# Power.net
KiCad netlist of a schematic drawn in Altium Designer
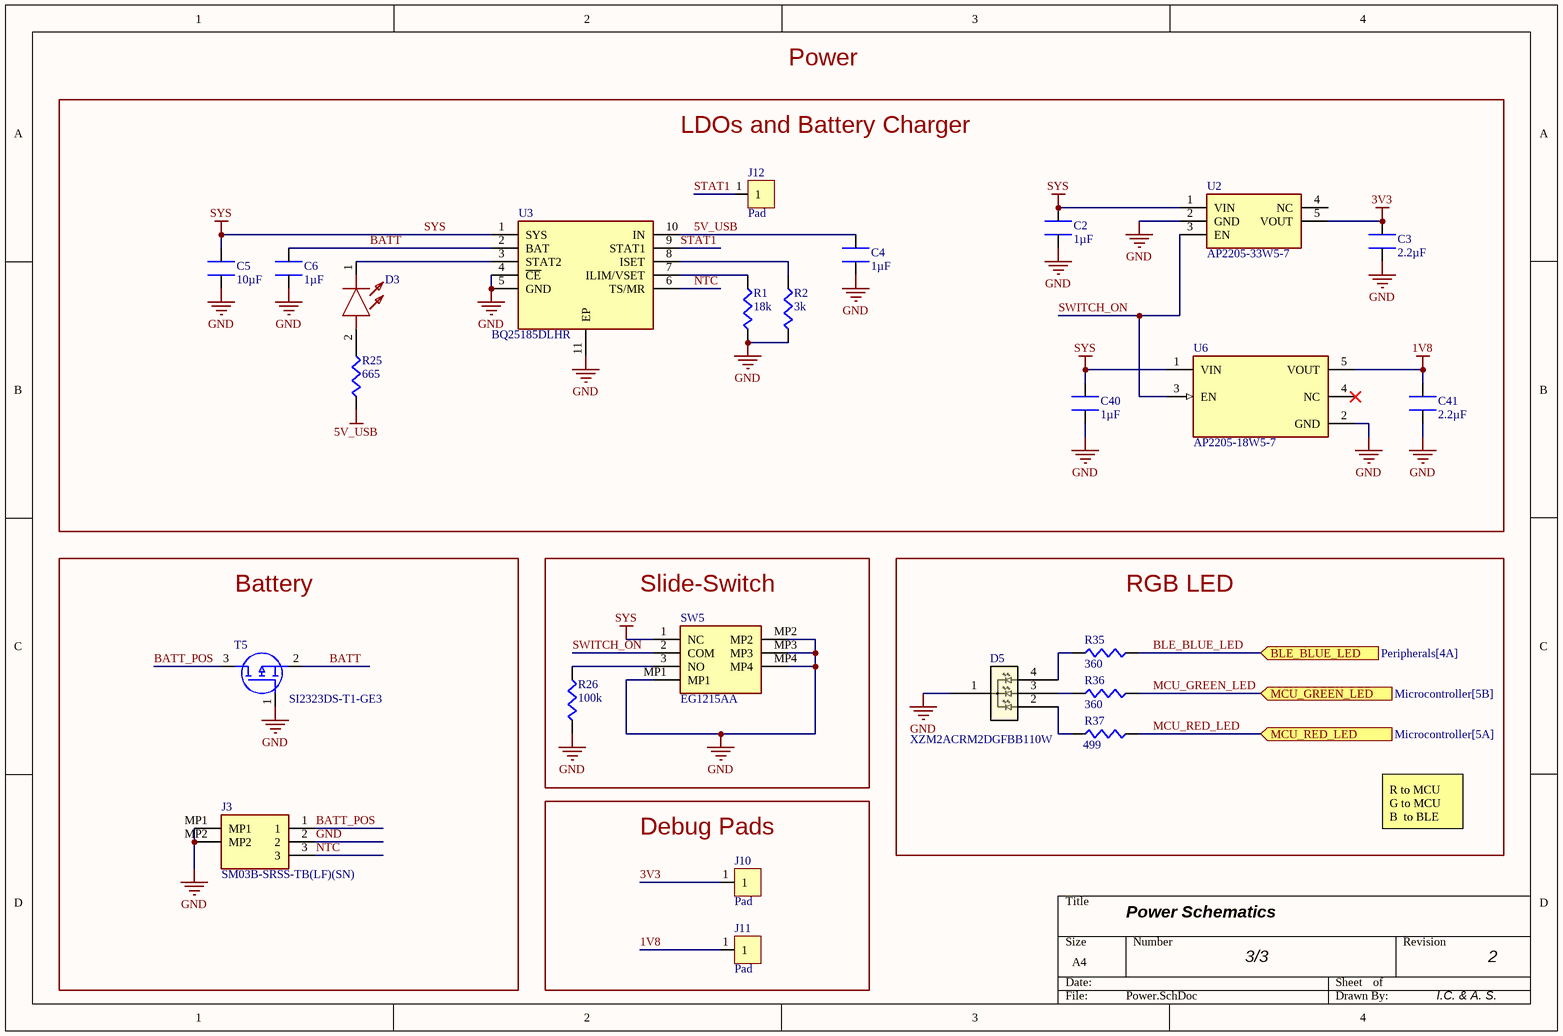
[diagram p0: Power.SchDoc]

(export (version "E")
  (design (tool "Eeschema 10.0.6"))
  (components
    (comp (ref "C2")
      (value "1µF")
      (footprint "Chip2PinSM127P600-8N")
      (fields (field (name "Comment") "0402YD105KAT4A"))
      (libsource (lib "Workspace LAB SEL") (part "Generic capacitor"))
    )
    (comp (ref "C3")
      (value "2.2µF")
      (footprint "Chip2PinSM127P600-8N")
      (fields (field (name "Comment") "LMK105BJ225MV-F"))
      (libsource (lib "Workspace LAB SEL") (part "Generic capacitor"))
    )
    (comp (ref "C4")
      (value "1µF")
      (footprint "Chip2PinSM127P600-8N")
      (fields (field (name "Comment") "CL03A105KP3NSNC"))
      (libsource (lib "Workspace LAB SEL") (part "Generic capacitor"))
    )
    (comp (ref "C5")
      (value "10µF")
      (footprint "Chip2PinSM127P600-8N")
      (fields (field (name "Comment") "0402ZD106MAT2A"))
      (libsource (lib "Workspace LAB SEL") (part "Generic capacitor"))
    )
    (comp (ref "C6")
      (value "1µF")
      (footprint "Chip2PinSM127P600-8N")
      (fields (field (name "Comment") "CL03A105KP3NSNC"))
      (libsource (lib "Workspace LAB SEL") (part "Generic capacitor"))
    )
    (comp (ref "C40")
      (value "1µF")
      (footprint "Chip2PinSM127P600-8N")
      (fields (field (name "Comment") "0402YD105KAT4A"))
      (libsource (lib "Workspace LAB SEL") (part "Generic capacitor"))
    )
    (comp (ref "C41")
      (value "2.2µF")
      (footprint "Chip2PinSM127P600-8N")
      (fields (field (name "Comment") "LMK105BJ225MV-F"))
      (libsource (lib "Workspace LAB SEL") (part "Generic capacitor"))
    )
    (comp (ref "D3")
      (value "KS EELP41.22-P1R2-58-A8J8-020-R18")
      (footprint "KS EELP41.22-P1R2-58-A8J8-020-R18-Footprint-1")
      (description "Single Colour LEDs")
      (libsource (lib "Workspace LAB SEL") (part "KS EELP41.22-P1R2-58-A8J8-020-R18-Symbol-1"))
    )
    (comp (ref "D5")
      (value "XZM2ACRM2DGFBB110W")
      (footprint "XZM2ACRM2DGFBB110W-Footprint-1")
      (description "1.6X1.6MM Rgb Full Color SMD Led")
      (libsource (lib "Workspace LAB SEL") (part "XZM2ACRM2DGFBB110W-Symbol-1"))
    )
    (comp (ref "J3")
      (value "SM03B-SRSS-TB(LF)(SN)")
      (footprint "SM03B-SRSS-TB(LF)(SN)-Footprint-1")
      (description "Connector Header, Side Entry, SR Series, 3 Position, 1.00mm, 50V, Surface Mount, Tin, Natural")
      (libsource (lib "Workspace LAB SEL") (part "SM03B-SRSS-TB(LF)(SN)-Symbol-1"))
    )
    (comp (ref "J10")
      (value "Pad")
      (footprint "Pad-Footprint-1")
      (description "Pad to connect external electrodes or sensors. Choose the right footprint.")
      (libsource (lib "Workspace LAB SEL") (part "Pad-Symbol-1"))
    )
    (comp (ref "J11")
      (value "Pad")
      (footprint "Pad-Footprint-1")
      (description "Pad to connect external electrodes or sensors. Choose the right footprint.")
      (libsource (lib "Workspace LAB SEL") (part "Pad-Symbol-1"))
    )
    (comp (ref "J12")
      (value "Pad")
      (footprint "Pad-Footprint-1")
      (description "Pad to connect external electrodes or sensors. Choose the right footprint.")
      (libsource (lib "Workspace LAB SEL") (part "Pad-Symbol-1"))
    )
    (comp (ref "R1")
      (value "18k")
      (footprint "Chip2PinSM127P600-8N")
      (description "Fixed Resistor, Thin Film, 0.05W, 18000ohm, 25V, 0.1% +/-Tol, 25ppm/Cel, Surface Mount, 0201")
      (fields (field (name "TOLERANCE") "0.1%") (field (name "Comment") "TNPW020118K0BEED"))
      (libsource (lib "Workspace LAB SEL") (part "Generic resistor"))
    )
    (comp (ref "R2")
      (value "3k")
      (footprint "Chip2PinSM127P600-8N")
      (description "Fixed Resistor, Thin Film, 0.05W, 3000ohm, 25V, 0.1% +/-Tol, 25ppm/Cel, Surface Mount, 0201")
      (fields (field (name "TOLERANCE") "0.1%") (field (name "Comment") "TNPW02013K00BEED"))
      (libsource (lib "Workspace LAB SEL") (part "Generic resistor"))
    )
    (comp (ref "R25")
      (value "665")
      (footprint "Chip2PinSM127P600-8N")
      (fields
        (field (name "TOLERANCE") "1%")
        (field (name "POWER") "50mW")
        (field (name "Comment") "CRCW0201665RFKED")
      )
      (libsource (lib "Workspace LAB SEL") (part "Generic resistor"))
    )
    (comp (ref "R26")
      (value "100k")
      (footprint "Chip2PinSM127P600-8N")
      (fields
        (field (name "POWER") "50mW")
        (field (name "TOLERANCE") "5%")
        (field (name "Comment") "ERJ-1GNJ104C")
      )
      (libsource (lib "Workspace LAB SEL") (part "Generic resistor"))
    )
    (comp (ref "R35")
      (value "360")
      (footprint "Chip2PinSM127P600-8N")
      (fields
        (field (name "TOLERANCE") "1%")
        (field (name "POWER") "50mW")
        (field (name "Comment") "CRCW0201360RFKED")
      )
      (libsource (lib "Workspace LAB SEL") (part "Generic resistor"))
    )
    (comp (ref "R36")
      (value "360")
      (footprint "Chip2PinSM127P600-8N")
      (fields
        (field (name "TOLERANCE") "1%")
        (field (name "POWER") "50mW")
        (field (name "Comment") "CRCW0201360RFKED")
      )
      (libsource (lib "Workspace LAB SEL") (part "Generic resistor"))
    )
    (comp (ref "R37")
      (value "499")
      (footprint "Chip2PinSM127P600-8N")
      (description "0201 Thin film chip resistor 0201 SMD Resistor 0.1% 25ppm 499ohm")
      (fields (field (name "Comment") "ERA-1AEB4990C"))
      (libsource (lib "Workspace LAB SEL") (part "Generic resistor"))
    )
    (comp (ref "SW5")
      (value "EG1215AA")
      (footprint "EG1215AA-Footprint-1")
      (description "Slide Switch")
      (libsource (lib "Workspace LAB SEL") (part "EG1215AA-Symbol-1"))
    )
    (comp (ref "T5")
      (value "SI2323DS-T1-GE3")
      (footprint "SI2323DS-T1-GE3-Footprint-1")
      (libsource (lib "Workspace LAB SEL") (part "SI2323DS-T1-GE3-Symbol-1"))
    )
    (comp (ref "U2")
      (value "AP2205-33W5-7")
      (footprint "AP2205-33W5-7-Footprint-1")
      (description "Fixed LDO Voltage Regulator, 2.3V to 24V in, 360mV Drop, 3.3V out, 200mA out, SOT-25-5")
      (libsource (lib "Workspace LAB SEL") (part "AP2205-33W5-7-Symbol-1"))
    )
    (comp (ref "U3")
      (value "BQ25185DLHR")
      (footprint "BQ25185DLHR-Footprint-1")
      (libsource (lib "Workspace LAB SEL") (part "BQ25185DLHR-Symbol-1"))
    )
    (comp (ref "U6")
      (value "AP2205-18W5-7")
      (footprint "AP2205-18W5-7-Footprint-1")
      (description "LDO Voltage Regulators LDO CMOS LowCurr. 1.8V fixed")
      (libsource (lib "Workspace LAB SEL") (part "AP2205-18W5-7-Symbol-1"))
    )
  )
  (nets
    (net (code "1") (name "/BATT") (class "Default")
      (node (ref "C6") (pin "2") (pinfunction "2_2") (pintype "passive"))
      (node (ref "T5") (pin "2") (pinfunction "S_2") (pintype "passive"))
      (node (ref "U3") (pin "2") (pinfunction "BAT_2") (pintype "passive"))
    )
    (net (code "2") (name "/BATT_POS") (class "Default")
      (node (ref "J3") (pin "1") (pinfunction "1_1") (pintype "passive"))
      (node (ref "T5") (pin "3") (pinfunction "D_3") (pintype "passive"))
    )
    (net (code "3") (name "/BLE_BLUE_LED") (class "Default")
      (node (ref "R35") (pin "2") (pinfunction "2_2") (pintype "passive"))
    )
    (net (code "4") (name "/MCU_GREEN_LED") (class "Default")
      (node (ref "R36") (pin "2") (pinfunction "2_2") (pintype "passive"))
    )
    (net (code "5") (name "/MCU_RED_LED") (class "Default")
      (node (ref "R37") (pin "2") (pinfunction "2_2") (pintype "passive"))
    )
    (net (code "6") (name "/NTC") (class "Default")
      (node (ref "J3") (pin "3") (pinfunction "3_3") (pintype "passive"))
      (node (ref "U3") (pin "6") (pinfunction "TS/MR_6") (pintype "passive"))
    )
    (net (code "7") (name "/STAT1") (class "Default")
      (node (ref "J12") (pin "1") (pinfunction "1_1") (pintype "passive"))
      (node (ref "U3") (pin "9") (pinfunction "STAT1_9") (pintype "passive"))
    )
    (net (code "8") (name "/SWITCH_ON") (class "Default")
      (node (ref "SW5") (pin "2") (pinfunction "COM_2") (pintype "passive"))
      (node (ref "U2") (pin "3") (pinfunction "EN_3") (pintype "passive"))
      (node (ref "U6") (pin "3") (pinfunction "EN_3") (pintype "input"))
    )
    (net (code "9") (name "1V8") (class "Default")
      (node (ref "C41") (pin "2") (pinfunction "2_2") (pintype "passive"))
      (node (ref "J11") (pin "1") (pinfunction "1_1") (pintype "passive"))
      (node (ref "U6") (pin "5") (pinfunction "VOUT_5") (pintype "power_in"))
    )
    (net (code "10") (name "3V3") (class "Default")
      (node (ref "C3") (pin "2") (pinfunction "2_2") (pintype "passive"))
      (node (ref "J10") (pin "1") (pinfunction "1_1") (pintype "passive"))
      (node (ref "U2") (pin "5") (pinfunction "VOUT_5") (pintype "passive"))
    )
    (net (code "11") (name "5V_USB") (class "Default")
      (node (ref "C4") (pin "2") (pinfunction "2_2") (pintype "passive"))
      (node (ref "R25") (pin "1") (pinfunction "1_1") (pintype "passive"))
      (node (ref "U3") (pin "10") (pinfunction "IN_10") (pintype "passive"))
    )
    (net (code "12") (name "GND") (class "Default")
      (node (ref "C2") (pin "1") (pinfunction "1_1") (pintype "passive"))
      (node (ref "C3") (pin "1") (pinfunction "1_1") (pintype "passive"))
      (node (ref "C4") (pin "1") (pinfunction "1_1") (pintype "passive"))
      (node (ref "C40") (pin "1") (pinfunction "1_1") (pintype "passive"))
      (node (ref "C41") (pin "1") (pinfunction "1_1") (pintype "passive"))
      (node (ref "C5") (pin "2") (pinfunction "2_2") (pintype "passive"))
      (node (ref "C6") (pin "1") (pinfunction "1_1") (pintype "passive"))
      (node (ref "D5") (pin "1") (pinfunction "1_1") (pintype "passive"))
      (node (ref "J3") (pin "2") (pinfunction "2_2") (pintype "passive"))
      (node (ref "J3") (pin "MP1") (pinfunction "MP1_MP1") (pintype "passive"))
      (node (ref "J3") (pin "MP2") (pinfunction "MP2_MP2") (pintype "passive"))
      (node (ref "R1") (pin "1") (pinfunction "1_1") (pintype "passive"))
      (node (ref "R2") (pin "1") (pinfunction "1_1") (pintype "passive"))
      (node (ref "R26") (pin "1") (pinfunction "1_1") (pintype "passive"))
      (node (ref "SW5") (pin "MP1") (pinfunction "MP1_MP1") (pintype "passive"))
      (node (ref "SW5") (pin "MP2") (pinfunction "MP2_MP2") (pintype "passive"))
      (node (ref "SW5") (pin "MP3") (pinfunction "MP3_MP3") (pintype "passive"))
      (node (ref "SW5") (pin "MP4") (pinfunction "MP4_MP4") (pintype "passive"))
      (node (ref "T5") (pin "1") (pinfunction "G_1") (pintype "passive"))
      (node (ref "U2") (pin "2") (pinfunction "GND_2") (pintype "passive"))
      (node (ref "U3") (pin "11") (pinfunction "EP_11") (pintype "passive"))
      (node (ref "U3") (pin "4") (pinfunction "~{CE}_4") (pintype "passive"))
      (node (ref "U3") (pin "5") (pinfunction "GND_5") (pintype "passive"))
      (node (ref "U6") (pin "2") (pinfunction "GND_2") (pintype "power_in"))
    )
    (net (code "13") (name "Net-(D3-A)") (class "Default")
      (node (ref "D3") (pin "2") (pinfunction "A_2") (pintype "passive"))
      (node (ref "R25") (pin "2") (pinfunction "2_2") (pintype "passive"))
    )
    (net (code "14") (name "Net-(D3-K)") (class "Default")
      (node (ref "D3") (pin "1") (pinfunction "K_1") (pintype "passive"))
      (node (ref "U3") (pin "3") (pinfunction "STAT2_3") (pintype "passive"))
    )
    (net (code "15") (name "Net-(D5-Pad2)") (class "Default")
      (node (ref "D5") (pin "2") (pinfunction "2_2") (pintype "passive"))
      (node (ref "R37") (pin "1") (pinfunction "1_1") (pintype "passive"))
    )
    (net (code "16") (name "Net-(D5-Pad3)") (class "Default")
      (node (ref "D5") (pin "3") (pinfunction "3_3") (pintype "passive"))
      (node (ref "R36") (pin "1") (pinfunction "1_1") (pintype "passive"))
    )
    (net (code "17") (name "Net-(D5-Pad4)") (class "Default")
      (node (ref "D5") (pin "4") (pinfunction "4_4") (pintype "passive"))
      (node (ref "R35") (pin "1") (pinfunction "1_1") (pintype "passive"))
    )
    (net (code "18") (name "Net-(SW5-NO)") (class "Default")
      (node (ref "R26") (pin "2") (pinfunction "2_2") (pintype "passive"))
      (node (ref "SW5") (pin "3") (pinfunction "NO_3") (pintype "passive"))
    )
    (net (code "19") (name "Net-(U3-ILIM{slash}VSET)") (class "Default")
      (node (ref "R1") (pin "2") (pinfunction "2_2") (pintype "passive"))
      (node (ref "U3") (pin "7") (pinfunction "ILIM/VSET_7") (pintype "passive"))
    )
    (net (code "20") (name "Net-(U3-ISET)") (class "Default")
      (node (ref "R2") (pin "2") (pinfunction "2_2") (pintype "passive"))
      (node (ref "U3") (pin "8") (pinfunction "ISET_8") (pintype "passive"))
    )
    (net (code "21") (name "SYS") (class "Default")
      (node (ref "C2") (pin "2") (pinfunction "2_2") (pintype "passive"))
      (node (ref "C40") (pin "2") (pinfunction "2_2") (pintype "passive"))
      (node (ref "C5") (pin "1") (pinfunction "1_1") (pintype "passive"))
      (node (ref "SW5") (pin "1") (pinfunction "NC_1") (pintype "passive"))
      (node (ref "U2") (pin "1") (pinfunction "VIN_1") (pintype "passive"))
      (node (ref "U3") (pin "1") (pinfunction "SYS_1") (pintype "passive"))
      (node (ref "U6") (pin "1") (pinfunction "VIN_1") (pintype "power_in"))
    )
    (net (code "22") (name "unconnected-(U2-NC-Pad4)") (class "Default")
      (node (ref "U2") (pin "4") (pinfunction "NC_4") (pintype "passive"))
    )
    (net (code "23") (name "unconnected-(U6-NC-Pad4)") (class "Default")
      (node (ref "U6") (pin "4") (pinfunction "NC_4") (pintype "passive+no_connect"))
    )
  )
)
